# main_adapter_board_2016.net
KiCad netlist of a schematic drawn in Altium Designer
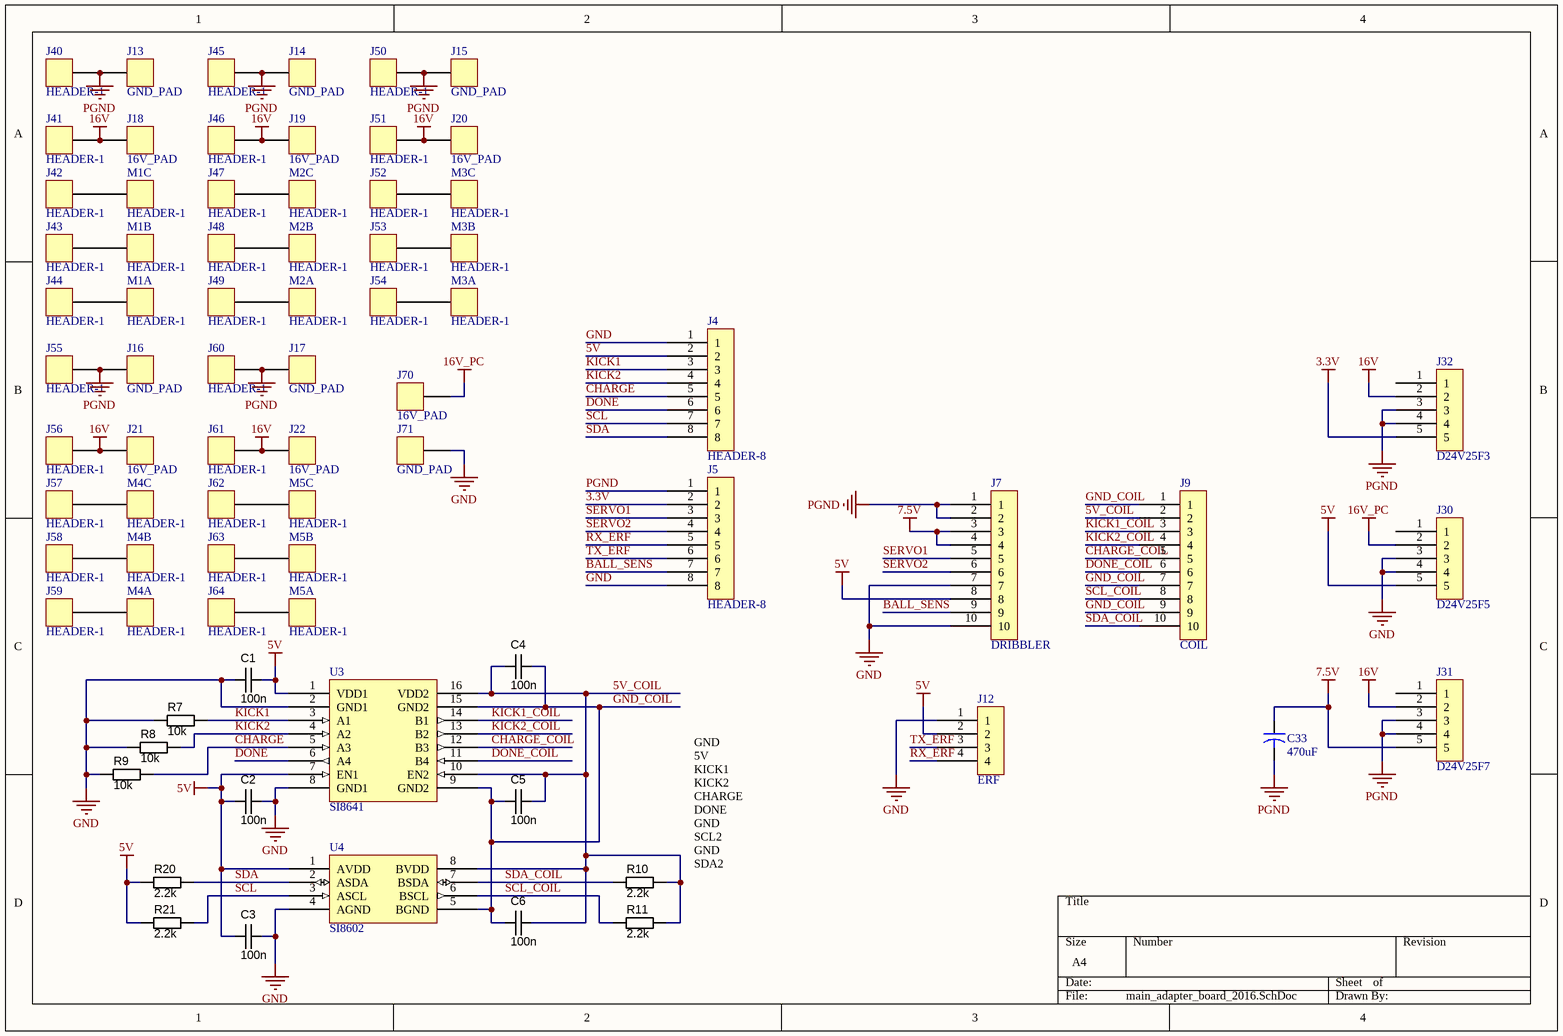
[diagram p0: main_adapter_board_2016.SchDoc]

(export (version "E")
  (design (tool "Eeschema 10.0.6"))
  (components
    (comp (ref "C1")
      (value "100n")
      (footprint "CAPC1608X90N")
      (description "Capacitor SMD Cer 100nF 10% 50V X7R 0603")
      (fields (field (name "TOLERANCE") "±10%"))
      (libsource (lib "PBL - Capacitors") (part "CAPC_100n_0603_X7R_50V_10%"))
    )
    (comp (ref "C2")
      (value "100n")
      (footprint "CAPC1608X90N")
      (description "Capacitor SMD Cer 100nF 10% 50V X7R 0603")
      (fields (field (name "TOLERANCE") "±10%"))
      (libsource (lib "PBL - Capacitors") (part "CAPC_100n_0603_X7R_50V_10%"))
    )
    (comp (ref "C3")
      (value "100n")
      (footprint "CAPC1608X90N")
      (description "Capacitor SMD Cer 100nF 10% 50V X7R 0603")
      (fields (field (name "TOLERANCE") "±10%"))
      (libsource (lib "PBL - Capacitors") (part "CAPC_100n_0603_X7R_50V_10%"))
    )
    (comp (ref "C4")
      (value "100n")
      (footprint "CAPC1608X90N")
      (description "Capacitor SMD Cer 100nF 10% 50V X7R 0603")
      (fields (field (name "TOLERANCE") "±10%"))
      (libsource (lib "PBL - Capacitors") (part "CAPC_100n_0603_X7R_50V_10%"))
    )
    (comp (ref "C5")
      (value "100n")
      (footprint "CAPC1608X90N")
      (description "Capacitor SMD Cer 100nF 10% 50V X7R 0603")
      (fields (field (name "TOLERANCE") "±10%"))
      (libsource (lib "PBL - Capacitors") (part "CAPC_100n_0603_X7R_50V_10%"))
    )
    (comp (ref "C6")
      (value "100n")
      (footprint "CAPC1608X90N")
      (description "Capacitor SMD Cer 100nF 10% 50V X7R 0603")
      (fields (field (name "TOLERANCE") "±10%"))
      (libsource (lib "PBL - Capacitors") (part "CAPC_100n_0603_X7R_50V_10%"))
    )
    (comp (ref "C33")
      (value "470uF")
      (footprint "CAPR5-4X5")
      (description "Capacitor")
      (fields (field (name "PUBLISHER") "Altium Limited"))
      (libsource (lib "Miscellaneous Devices") (part "Cap2"))
    )
    (comp (ref "J4")
      (value "HEADER-8")
      (footprint "MICRO-MATCH-8")
      (libsource (lib "connectors") (part "HEADER-8"))
    )
    (comp (ref "J5")
      (value "HEADER-8")
      (footprint "MICRO-MATCH-8")
      (libsource (lib "connectors") (part "HEADER-8"))
    )
    (comp (ref "J7")
      (value "DRIBBLER")
      (footprint "MICRO-MATCH-10")
      (libsource (lib "connectors") (part "HEADER-10"))
    )
    (comp (ref "J9")
      (value "COIL")
      (footprint "MICRO-MATCH-10")
      (libsource (lib "connectors") (part "HEADER-10"))
    )
    (comp (ref "J12")
      (value "ERF")
      (footprint "MICRO-MATCH-4")
      (libsource (lib "connectors") (part "HEADER-4"))
    )
    (comp (ref "J13")
      (value "GND_PAD")
      (footprint "POWER-PAD")
      (libsource (lib "connectors") (part "HEADER-1"))
    )
    (comp (ref "J14")
      (value "GND_PAD")
      (footprint "POWER-PAD")
      (libsource (lib "connectors") (part "HEADER-1"))
    )
    (comp (ref "J15")
      (value "GND_PAD")
      (footprint "POWER-PAD")
      (libsource (lib "connectors") (part "HEADER-1"))
    )
    (comp (ref "J16")
      (value "GND_PAD")
      (footprint "POWER-PAD")
      (libsource (lib "connectors") (part "HEADER-1"))
    )
    (comp (ref "J17")
      (value "GND_PAD")
      (footprint "POWER-PAD")
      (libsource (lib "connectors") (part "HEADER-1"))
    )
    (comp (ref "J18")
      (value "16V_PAD")
      (footprint "POWER-PAD")
      (libsource (lib "connectors") (part "HEADER-1"))
    )
    (comp (ref "J19")
      (value "16V_PAD")
      (footprint "POWER-PAD")
      (libsource (lib "connectors") (part "HEADER-1"))
    )
    (comp (ref "J20")
      (value "16V_PAD")
      (footprint "POWER-PAD")
      (libsource (lib "connectors") (part "HEADER-1"))
    )
    (comp (ref "J21")
      (value "16V_PAD")
      (footprint "POWER-PAD")
      (libsource (lib "connectors") (part "HEADER-1"))
    )
    (comp (ref "J22")
      (value "16V_PAD")
      (footprint "POWER-PAD")
      (libsource (lib "connectors") (part "HEADER-1"))
    )
    (comp (ref "J30")
      (value "D24V25F5")
      (footprint "PIN-HEADER-5")
      (libsource (lib "connectors") (part "HEADER-5"))
    )
    (comp (ref "J31")
      (value "D24V25F7")
      (footprint "PIN-HEADER-5")
      (libsource (lib "connectors") (part "HEADER-5"))
    )
    (comp (ref "J32")
      (value "D24V25F3")
      (footprint "PIN-HEADER-5")
      (libsource (lib "connectors") (part "HEADER-5"))
    )
    (comp (ref "J40")
      (value "HEADER-1")
      (footprint "2MM-BULLET-PLUG-VIA")
      (libsource (lib "") (part "HEADER-1_1"))
    )
    (comp (ref "J41")
      (value "HEADER-1")
      (footprint "2MM-BULLET-PLUG-VIA")
      (libsource (lib "") (part "HEADER-1_1"))
    )
    (comp (ref "J42")
      (value "HEADER-1")
      (footprint "2MM-BULLET-PLUG-VIA")
      (libsource (lib "") (part "HEADER-1_1"))
    )
    (comp (ref "J43")
      (value "HEADER-1")
      (footprint "2MM-BULLET-PLUG-VIA")
      (libsource (lib "") (part "HEADER-1_1"))
    )
    (comp (ref "J44")
      (value "HEADER-1")
      (footprint "2MM-BULLET-PLUG-VIA")
      (libsource (lib "") (part "HEADER-1_1"))
    )
    (comp (ref "J45")
      (value "HEADER-1")
      (footprint "2MM-BULLET-PLUG-VIA")
      (libsource (lib "") (part "HEADER-1_1"))
    )
    (comp (ref "J46")
      (value "HEADER-1")
      (footprint "2MM-BULLET-PLUG-VIA")
      (libsource (lib "") (part "HEADER-1_1"))
    )
    (comp (ref "J47")
      (value "HEADER-1")
      (footprint "2MM-BULLET-PLUG-VIA")
      (libsource (lib "") (part "HEADER-1_1"))
    )
    (comp (ref "J48")
      (value "HEADER-1")
      (footprint "2MM-BULLET-PLUG-VIA")
      (libsource (lib "") (part "HEADER-1_1"))
    )
    (comp (ref "J49")
      (value "HEADER-1")
      (footprint "2MM-BULLET-PLUG-VIA")
      (libsource (lib "") (part "HEADER-1_1"))
    )
    (comp (ref "J50")
      (value "HEADER-1")
      (footprint "2MM-BULLET-PLUG-VIA")
      (libsource (lib "") (part "HEADER-1_1"))
    )
    (comp (ref "J51")
      (value "HEADER-1")
      (footprint "2MM-BULLET-PLUG-VIA")
      (libsource (lib "") (part "HEADER-1_1"))
    )
    (comp (ref "J52")
      (value "HEADER-1")
      (footprint "2MM-BULLET-PLUG-VIA")
      (libsource (lib "") (part "HEADER-1_1"))
    )
    (comp (ref "J53")
      (value "HEADER-1")
      (footprint "2MM-BULLET-PLUG-VIA")
      (libsource (lib "") (part "HEADER-1_1"))
    )
    (comp (ref "J54")
      (value "HEADER-1")
      (footprint "2MM-BULLET-PLUG-VIA")
      (libsource (lib "") (part "HEADER-1_1"))
    )
    (comp (ref "J55")
      (value "HEADER-1")
      (footprint "2MM-BULLET-PLUG-VIA")
      (libsource (lib "") (part "HEADER-1_1"))
    )
    (comp (ref "J56")
      (value "HEADER-1")
      (footprint "2MM-BULLET-PLUG-VIA")
      (libsource (lib "") (part "HEADER-1_1"))
    )
    (comp (ref "J57")
      (value "HEADER-1")
      (footprint "2MM-BULLET-PLUG-VIA")
      (libsource (lib "") (part "HEADER-1_1"))
    )
    (comp (ref "J58")
      (value "HEADER-1")
      (footprint "2MM-BULLET-PLUG-VIA")
      (libsource (lib "") (part "HEADER-1_1"))
    )
    (comp (ref "J59")
      (value "HEADER-1")
      (footprint "2MM-BULLET-PLUG-VIA")
      (libsource (lib "") (part "HEADER-1_1"))
    )
    (comp (ref "J60")
      (value "HEADER-1")
      (footprint "2MM-BULLET-PLUG-VIA")
      (libsource (lib "") (part "HEADER-1_1"))
    )
    (comp (ref "J61")
      (value "HEADER-1")
      (footprint "2MM-BULLET-PLUG-VIA")
      (libsource (lib "") (part "HEADER-1_1"))
    )
    (comp (ref "J62")
      (value "HEADER-1")
      (footprint "2MM-BULLET-PLUG-VIA")
      (libsource (lib "") (part "HEADER-1_1"))
    )
    (comp (ref "J63")
      (value "HEADER-1")
      (footprint "2MM-BULLET-PLUG-VIA")
      (libsource (lib "") (part "HEADER-1_1"))
    )
    (comp (ref "J64")
      (value "HEADER-1")
      (footprint "2MM-BULLET-PLUG-VIA")
      (libsource (lib "") (part "HEADER-1_1"))
    )
    (comp (ref "J70") (value "16V_PAD") (footprint "POWER-PAD-4x3") (libsource (lib "") (part "HEADER-1_1")))
    (comp (ref "J71") (value "GND_PAD") (footprint "POWER-PAD-4x3") (libsource (lib "") (part "HEADER-1_1")))
    (comp (ref "M1A")
      (value "HEADER-1")
      (footprint "2MM-BULLET-VIA")
      (libsource (lib "connectors") (part "HEADER-1"))
    )
    (comp (ref "M1B")
      (value "HEADER-1")
      (footprint "2MM-BULLET-VIA")
      (libsource (lib "connectors") (part "HEADER-1"))
    )
    (comp (ref "M1C")
      (value "HEADER-1")
      (footprint "2MM-BULLET-VIA")
      (libsource (lib "connectors") (part "HEADER-1"))
    )
    (comp (ref "M2A")
      (value "HEADER-1")
      (footprint "2MM-BULLET-VIA")
      (libsource (lib "connectors") (part "HEADER-1"))
    )
    (comp (ref "M2B")
      (value "HEADER-1")
      (footprint "2MM-BULLET-VIA")
      (libsource (lib "connectors") (part "HEADER-1"))
    )
    (comp (ref "M2C")
      (value "HEADER-1")
      (footprint "2MM-BULLET-VIA")
      (libsource (lib "connectors") (part "HEADER-1"))
    )
    (comp (ref "M3A")
      (value "HEADER-1")
      (footprint "2MM-BULLET-VIA")
      (libsource (lib "connectors") (part "HEADER-1"))
    )
    (comp (ref "M3B")
      (value "HEADER-1")
      (footprint "2MM-BULLET-VIA")
      (libsource (lib "connectors") (part "HEADER-1"))
    )
    (comp (ref "M3C")
      (value "HEADER-1")
      (footprint "2MM-BULLET-VIA")
      (libsource (lib "connectors") (part "HEADER-1"))
    )
    (comp (ref "M4A")
      (value "HEADER-1")
      (footprint "2MM-BULLET-VIA")
      (libsource (lib "connectors") (part "HEADER-1"))
    )
    (comp (ref "M4B")
      (value "HEADER-1")
      (footprint "2MM-BULLET-VIA")
      (libsource (lib "connectors") (part "HEADER-1"))
    )
    (comp (ref "M4C")
      (value "HEADER-1")
      (footprint "2MM-BULLET-VIA")
      (libsource (lib "connectors") (part "HEADER-1"))
    )
    (comp (ref "M5A")
      (value "HEADER-1")
      (footprint "2MM-BULLET-VIA")
      (libsource (lib "connectors") (part "HEADER-1"))
    )
    (comp (ref "M5B")
      (value "HEADER-1")
      (footprint "2MM-BULLET-VIA")
      (libsource (lib "connectors") (part "HEADER-1"))
    )
    (comp (ref "M5C")
      (value "HEADER-1")
      (footprint "2MM-BULLET-VIA")
      (libsource (lib "connectors") (part "HEADER-1"))
    )
    (comp (ref "R7")
      (value "10k")
      (footprint "RESC1608X55N")
      (description "Resistor SMD chip 120 Ohm 0.1W 5% 0603")
      (fields (field (name "TOLERANCE") "±5%"))
      (libsource (lib "PBL - Resistors") (part "RES_120R_0603_5%"))
    )
    (comp (ref "R8")
      (value "10k")
      (footprint "RESC1608X55N")
      (description "Resistor SMD chip 120 Ohm 0.1W 5% 0603")
      (fields (field (name "TOLERANCE") "±5%"))
      (libsource (lib "PBL - Resistors") (part "RES_120R_0603_5%"))
    )
    (comp (ref "R9")
      (value "10k")
      (footprint "RESC1608X55N")
      (description "Resistor SMD chip 120 Ohm 0.1W 5% 0603")
      (fields (field (name "TOLERANCE") "±5%"))
      (libsource (lib "PBL - Resistors") (part "RES_120R_0603_5%"))
    )
    (comp (ref "R10")
      (value "2.2k")
      (footprint "RESC1608X55N")
      (description "Resistor SMD chip 120 Ohm 0.1W 5% 0603")
      (fields (field (name "TOLERANCE") "±5%"))
      (libsource (lib "PBL - Resistors") (part "RES_120R_0603_5%"))
    )
    (comp (ref "R11")
      (value "2.2k")
      (footprint "RESC1608X55N")
      (description "Resistor SMD chip 120 Ohm 0.1W 5% 0603")
      (fields (field (name "TOLERANCE") "±5%"))
      (libsource (lib "PBL - Resistors") (part "RES_120R_0603_5%"))
    )
    (comp (ref "R20")
      (value "2.2k")
      (footprint "RESC1608X55N")
      (description "Resistor SMD chip 120 Ohm 0.1W 5% 0603")
      (fields (field (name "TOLERANCE") "±5%"))
      (libsource (lib "PBL - Resistors") (part "RES_120R_0603_5%"))
    )
    (comp (ref "R21")
      (value "2.2k")
      (footprint "RESC1608X55N")
      (description "Resistor SMD chip 120 Ohm 0.1W 5% 0603")
      (fields (field (name "TOLERANCE") "±5%"))
      (libsource (lib "PBL - Resistors") (part "RES_120R_0603_5%"))
    )
    (comp (ref "U3") (value "SI8641") (footprint "SOIC16") (libsource (lib "digital") (part "SI8641")))
    (comp (ref "U4") (value "SI8602") (footprint "SOIC8") (libsource (lib "digital") (part "SI8602")))
  )
  (nets
    (net (code "1") (name "/5V_COIL") (class "Default")
      (node (ref "C4") (pin "2") (pintype "passive"))
      (node (ref "C5") (pin "1") (pintype "passive"))
      (node (ref "C6") (pin "1") (pintype "passive"))
      (node (ref "J9") (pin "2") (pinfunction "2_2") (pintype "passive"))
      (node (ref "R10") (pin "2") (pinfunction "2_2") (pintype "passive"))
      (node (ref "R11") (pin "2") (pinfunction "2_2") (pintype "passive"))
      (node (ref "U3") (pin "10") (pinfunction "EN2_10") (pintype "input"))
      (node (ref "U3") (pin "16") (pinfunction "VDD2_16") (pintype "power_in"))
      (node (ref "U4") (pin "8") (pinfunction "BVDD_8") (pintype "power_in"))
    )
    (net (code "2") (name "/BALL_SENS") (class "Default")
      (node (ref "J5") (pin "7") (pinfunction "7_7") (pintype "passive"))
      (node (ref "J7") (pin "9") (pinfunction "9_9") (pintype "passive"))
    )
    (net (code "3") (name "/CHARGE") (class "Default")
      (node (ref "J4") (pin "5") (pinfunction "5_5") (pintype "passive"))
      (node (ref "R9") (pin "2") (pinfunction "2_2") (pintype "passive"))
      (node (ref "U3") (pin "5") (pinfunction "A3_5") (pintype "input"))
    )
    (net (code "4") (name "/CHARGE_COIL") (class "Default")
      (node (ref "J9") (pin "5") (pinfunction "5_5") (pintype "passive"))
      (node (ref "U3") (pin "12") (pinfunction "B3_12") (pintype "output"))
    )
    (net (code "5") (name "/DONE") (class "Default")
      (node (ref "J4") (pin "6") (pinfunction "6_6") (pintype "passive"))
      (node (ref "U3") (pin "6") (pinfunction "A4_6") (pintype "output"))
    )
    (net (code "6") (name "/DONE_COIL") (class "Default")
      (node (ref "J9") (pin "6") (pinfunction "6_6") (pintype "passive"))
      (node (ref "U3") (pin "11") (pinfunction "B4_11") (pintype "input"))
    )
    (net (code "7") (name "/GND_COIL") (class "Default")
      (node (ref "C4") (pin "1") (pintype "passive"))
      (node (ref "C5") (pin "2") (pintype "passive"))
      (node (ref "C6") (pin "2") (pintype "passive"))
      (node (ref "J9") (pin "1") (pinfunction "1_1") (pintype "passive"))
      (node (ref "J9") (pin "7") (pinfunction "7_7") (pintype "passive"))
      (node (ref "J9") (pin "9") (pinfunction "9_9") (pintype "passive"))
      (node (ref "U3") (pin "15") (pinfunction "GND2_15") (pintype "power_in"))
      (node (ref "U3") (pin "9") (pinfunction "GND2_9") (pintype "power_in"))
      (node (ref "U4") (pin "5") (pinfunction "BGND_5") (pintype "power_in"))
    )
    (net (code "8") (name "/KICK1") (class "Default")
      (node (ref "J4") (pin "3") (pinfunction "3_3") (pintype "passive"))
      (node (ref "R7") (pin "2") (pinfunction "2_2") (pintype "passive"))
      (node (ref "U3") (pin "3") (pinfunction "A1_3") (pintype "input"))
    )
    (net (code "9") (name "/KICK1_COIL") (class "Default")
      (node (ref "J9") (pin "3") (pinfunction "3_3") (pintype "passive"))
      (node (ref "U3") (pin "14") (pinfunction "B1_14") (pintype "output"))
    )
    (net (code "10") (name "/KICK2") (class "Default")
      (node (ref "J4") (pin "4") (pinfunction "4_4") (pintype "passive"))
      (node (ref "R8") (pin "2") (pinfunction "2_2") (pintype "passive"))
      (node (ref "U3") (pin "4") (pinfunction "A2_4") (pintype "input"))
    )
    (net (code "11") (name "/KICK2_COIL") (class "Default")
      (node (ref "J9") (pin "4") (pinfunction "4_4") (pintype "passive"))
      (node (ref "U3") (pin "13") (pinfunction "B2_13") (pintype "output"))
    )
    (net (code "12") (name "/RX_ERF") (class "Default")
      (node (ref "J12") (pin "4") (pinfunction "4_4") (pintype "passive"))
      (node (ref "J5") (pin "5") (pinfunction "5_5") (pintype "passive"))
    )
    (net (code "13") (name "/SCL") (class "Default")
      (node (ref "J4") (pin "7") (pinfunction "7_7") (pintype "passive"))
      (node (ref "R21") (pin "2") (pinfunction "2_2") (pintype "passive"))
      (node (ref "U4") (pin "3") (pinfunction "ASCL_3") (pintype "input"))
    )
    (net (code "14") (name "/SCL_COIL") (class "Default")
      (node (ref "J9") (pin "8") (pinfunction "8_8") (pintype "passive"))
      (node (ref "R11") (pin "1") (pinfunction "1_1") (pintype "passive"))
      (node (ref "U4") (pin "6") (pinfunction "BSCL_6") (pintype "output"))
    )
    (net (code "15") (name "/SDA") (class "Default")
      (node (ref "J4") (pin "8") (pinfunction "8_8") (pintype "passive"))
      (node (ref "R20") (pin "2") (pinfunction "2_2") (pintype "passive"))
      (node (ref "U4") (pin "2") (pinfunction "ASDA_2") (pintype "bidirectional"))
    )
    (net (code "16") (name "/SDA_COIL") (class "Default")
      (node (ref "J9") (pin "10") (pinfunction "10_10") (pintype "passive"))
      (node (ref "R10") (pin "1") (pinfunction "1_1") (pintype "passive"))
      (node (ref "U4") (pin "7") (pinfunction "BSDA_7") (pintype "bidirectional"))
    )
    (net (code "17") (name "/SERVO1") (class "Default")
      (node (ref "J5") (pin "3") (pinfunction "3_3") (pintype "passive"))
      (node (ref "J7") (pin "5") (pinfunction "5_5") (pintype "passive"))
    )
    (net (code "18") (name "/SERVO2") (class "Default")
      (node (ref "J5") (pin "4") (pinfunction "4_4") (pintype "passive"))
      (node (ref "J7") (pin "6") (pinfunction "6_6") (pintype "passive"))
    )
    (net (code "19") (name "/TX_ERF") (class "Default")
      (node (ref "J12") (pin "3") (pinfunction "3_3") (pintype "passive"))
      (node (ref "J5") (pin "6") (pinfunction "6_6") (pintype "passive"))
    )
    (net (code "20") (name "3.3V") (class "Default")
      (node (ref "J32") (pin "5") (pinfunction "5_5") (pintype "passive"))
      (node (ref "J5") (pin "2") (pinfunction "2_2") (pintype "passive"))
    )
    (net (code "21") (name "5V") (class "Default")
      (node (ref "C1") (pin "1") (pintype "passive"))
      (node (ref "C2") (pin "2") (pintype "passive"))
      (node (ref "C3") (pin "2") (pintype "passive"))
      (node (ref "J12") (pin "2") (pinfunction "2_2") (pintype "passive"))
      (node (ref "J30") (pin "5") (pinfunction "5_5") (pintype "passive"))
      (node (ref "J4") (pin "2") (pinfunction "2_2") (pintype "passive"))
      (node (ref "J7") (pin "8") (pinfunction "8_8") (pintype "passive"))
      (node (ref "R20") (pin "1") (pinfunction "1_1") (pintype "passive"))
      (node (ref "R21") (pin "1") (pinfunction "1_1") (pintype "passive"))
      (node (ref "U3") (pin "1") (pinfunction "VDD1_1") (pintype "power_in"))
      (node (ref "U3") (pin "7") (pinfunction "EN1_7") (pintype "input"))
      (node (ref "U4") (pin "1") (pinfunction "AVDD_1") (pintype "power_in"))
    )
    (net (code "22") (name "7.5V") (class "Default")
      (node (ref "C33") (pin "1") (pinfunction "1_1") (pintype "passive"))
      (node (ref "J31") (pin "5") (pinfunction "5_5") (pintype "passive"))
      (node (ref "J7") (pin "3") (pinfunction "3_3") (pintype "passive"))
      (node (ref "J7") (pin "4") (pinfunction "4_4") (pintype "passive"))
    )
    (net (code "23") (name "16V") (class "Default")
      (node (ref "J18") (pin "1") (pinfunction "1_1") (pintype "passive"))
      (node (ref "J19") (pin "1") (pinfunction "1_1") (pintype "passive"))
      (node (ref "J20") (pin "1") (pinfunction "1_1") (pintype "passive"))
      (node (ref "J21") (pin "1") (pinfunction "1_1") (pintype "passive"))
      (node (ref "J22") (pin "1") (pinfunction "1_1") (pintype "passive"))
      (node (ref "J31") (pin "2") (pinfunction "2_2") (pintype "passive"))
      (node (ref "J32") (pin "2") (pinfunction "2_2") (pintype "passive"))
      (node (ref "J41") (pin "1") (pinfunction "1_1") (pintype "passive"))
      (node (ref "J46") (pin "1") (pinfunction "1_1") (pintype "passive"))
      (node (ref "J51") (pin "1") (pinfunction "1_1") (pintype "passive"))
      (node (ref "J56") (pin "1") (pinfunction "1_1") (pintype "passive"))
      (node (ref "J61") (pin "1") (pinfunction "1_1") (pintype "passive"))
    )
    (net (code "24") (name "16V_PC") (class "Default")
      (node (ref "J30") (pin "2") (pinfunction "2_2") (pintype "passive"))
      (node (ref "J70") (pin "1") (pinfunction "1_1") (pintype "passive"))
    )
    (net (code "25") (name "GND") (class "Default")
      (node (ref "C1") (pin "2") (pintype "passive"))
      (node (ref "C2") (pin "1") (pintype "passive"))
      (node (ref "C3") (pin "1") (pintype "passive"))
      (node (ref "J12") (pin "1") (pinfunction "1_1") (pintype "passive"))
      (node (ref "J30") (pin "3") (pinfunction "3_3") (pintype "passive"))
      (node (ref "J30") (pin "4") (pinfunction "4_4") (pintype "passive"))
      (node (ref "J4") (pin "1") (pinfunction "1_1") (pintype "passive"))
      (node (ref "J5") (pin "8") (pinfunction "8_8") (pintype "passive"))
      (node (ref "J7") (pin "10") (pinfunction "10_10") (pintype "passive"))
      (node (ref "J7") (pin "7") (pinfunction "7_7") (pintype "passive"))
      (node (ref "J71") (pin "1") (pinfunction "1_1") (pintype "passive"))
      (node (ref "R7") (pin "1") (pinfunction "1_1") (pintype "passive"))
      (node (ref "R8") (pin "1") (pinfunction "1_1") (pintype "passive"))
      (node (ref "R9") (pin "1") (pinfunction "1_1") (pintype "passive"))
      (node (ref "U3") (pin "2") (pinfunction "GND1_2") (pintype "power_in"))
      (node (ref "U3") (pin "8") (pinfunction "GND1_8") (pintype "power_in"))
      (node (ref "U4") (pin "4") (pinfunction "AGND_4") (pintype "power_in"))
    )
    (net (code "26") (name "Net-(J42-Pad1)") (class "Default")
      (node (ref "J42") (pin "1") (pinfunction "1_1") (pintype "passive"))
      (node (ref "M1C") (pin "1") (pinfunction "1_1") (pintype "passive"))
    )
    (net (code "27") (name "Net-(J43-Pad1)") (class "Default")
      (node (ref "J43") (pin "1") (pinfunction "1_1") (pintype "passive"))
      (node (ref "M1B") (pin "1") (pinfunction "1_1") (pintype "passive"))
    )
    (net (code "28") (name "Net-(J44-Pad1)") (class "Default")
      (node (ref "J44") (pin "1") (pinfunction "1_1") (pintype "passive"))
      (node (ref "M1A") (pin "1") (pinfunction "1_1") (pintype "passive"))
    )
    (net (code "29") (name "Net-(J47-Pad1)") (class "Default")
      (node (ref "J47") (pin "1") (pinfunction "1_1") (pintype "passive"))
      (node (ref "M2C") (pin "1") (pinfunction "1_1") (pintype "passive"))
    )
    (net (code "30") (name "Net-(J48-Pad1)") (class "Default")
      (node (ref "J48") (pin "1") (pinfunction "1_1") (pintype "passive"))
      (node (ref "M2B") (pin "1") (pinfunction "1_1") (pintype "passive"))
    )
    (net (code "31") (name "Net-(J49-Pad1)") (class "Default")
      (node (ref "J49") (pin "1") (pinfunction "1_1") (pintype "passive"))
      (node (ref "M2A") (pin "1") (pinfunction "1_1") (pintype "passive"))
    )
    (net (code "32") (name "Net-(J52-Pad1)") (class "Default")
      (node (ref "J52") (pin "1") (pinfunction "1_1") (pintype "passive"))
      (node (ref "M3C") (pin "1") (pinfunction "1_1") (pintype "passive"))
    )
    (net (code "33") (name "Net-(J53-Pad1)") (class "Default")
      (node (ref "J53") (pin "1") (pinfunction "1_1") (pintype "passive"))
      (node (ref "M3B") (pin "1") (pinfunction "1_1") (pintype "passive"))
    )
    (net (code "34") (name "Net-(J54-Pad1)") (class "Default")
      (node (ref "J54") (pin "1") (pinfunction "1_1") (pintype "passive"))
      (node (ref "M3A") (pin "1") (pinfunction "1_1") (pintype "passive"))
    )
    (net (code "35") (name "Net-(J57-Pad1)") (class "Default")
      (node (ref "J57") (pin "1") (pinfunction "1_1") (pintype "passive"))
      (node (ref "M4C") (pin "1") (pinfunction "1_1") (pintype "passive"))
    )
    (net (code "36") (name "Net-(J58-Pad1)") (class "Default")
      (node (ref "J58") (pin "1") (pinfunction "1_1") (pintype "passive"))
      (node (ref "M4B") (pin "1") (pinfunction "1_1") (pintype "passive"))
    )
    (net (code "37") (name "Net-(J59-Pad1)") (class "Default")
      (node (ref "J59") (pin "1") (pinfunction "1_1") (pintype "passive"))
      (node (ref "M4A") (pin "1") (pinfunction "1_1") (pintype "passive"))
    )
    (net (code "38") (name "Net-(J62-Pad1)") (class "Default")
      (node (ref "J62") (pin "1") (pinfunction "1_1") (pintype "passive"))
      (node (ref "M5C") (pin "1") (pinfunction "1_1") (pintype "passive"))
    )
    (net (code "39") (name "Net-(J63-Pad1)") (class "Default")
      (node (ref "J63") (pin "1") (pinfunction "1_1") (pintype "passive"))
      (node (ref "M5B") (pin "1") (pinfunction "1_1") (pintype "passive"))
    )
    (net (code "40") (name "Net-(J64-Pad1)") (class "Default")
      (node (ref "J64") (pin "1") (pinfunction "1_1") (pintype "passive"))
      (node (ref "M5A") (pin "1") (pinfunction "1_1") (pintype "passive"))
    )
    (net (code "41") (name "PGND") (class "Default")
      (node (ref "C33") (pin "2") (pinfunction "2_2") (pintype "passive"))
      (node (ref "J13") (pin "1") (pinfunction "1_1") (pintype "passive"))
      (node (ref "J14") (pin "1") (pinfunction "1_1") (pintype "passive"))
      (node (ref "J15") (pin "1") (pinfunction "1_1") (pintype "passive"))
      (node (ref "J16") (pin "1") (pinfunction "1_1") (pintype "passive"))
      (node (ref "J17") (pin "1") (pinfunction "1_1") (pintype "passive"))
      (node (ref "J31") (pin "3") (pinfunction "3_3") (pintype "passive"))
      (node (ref "J31") (pin "4") (pinfunction "4_4") (pintype "passive"))
      (node (ref "J32") (pin "3") (pinfunction "3_3") (pintype "passive"))
      (node (ref "J32") (pin "4") (pinfunction "4_4") (pintype "passive"))
      (node (ref "J40") (pin "1") (pinfunction "1_1") (pintype "passive"))
      (node (ref "J45") (pin "1") (pinfunction "1_1") (pintype "passive"))
      (node (ref "J5") (pin "1") (pinfunction "1_1") (pintype "passive"))
      (node (ref "J50") (pin "1") (pinfunction "1_1") (pintype "passive"))
      (node (ref "J55") (pin "1") (pinfunction "1_1") (pintype "passive"))
      (node (ref "J60") (pin "1") (pinfunction "1_1") (pintype "passive"))
      (node (ref "J7") (pin "1") (pinfunction "1_1") (pintype "passive"))
      (node (ref "J7") (pin "2") (pinfunction "2_2") (pintype "passive"))
    )
    (net (code "42") (name "unconnected-(J30-Pad1)") (class "Default")
      (node (ref "J30") (pin "1") (pinfunction "1_1") (pintype "passive"))
    )
    (net (code "43") (name "unconnected-(J31-Pad1)") (class "Default")
      (node (ref "J31") (pin "1") (pinfunction "1_1") (pintype "passive"))
    )
    (net (code "44") (name "unconnected-(J32-Pad1)") (class "Default")
      (node (ref "J32") (pin "1") (pinfunction "1_1") (pintype "passive"))
    )
  )
)
